# C64_Keyb-Test.net
KiCad netlist of a schematic drawn in EAGLE
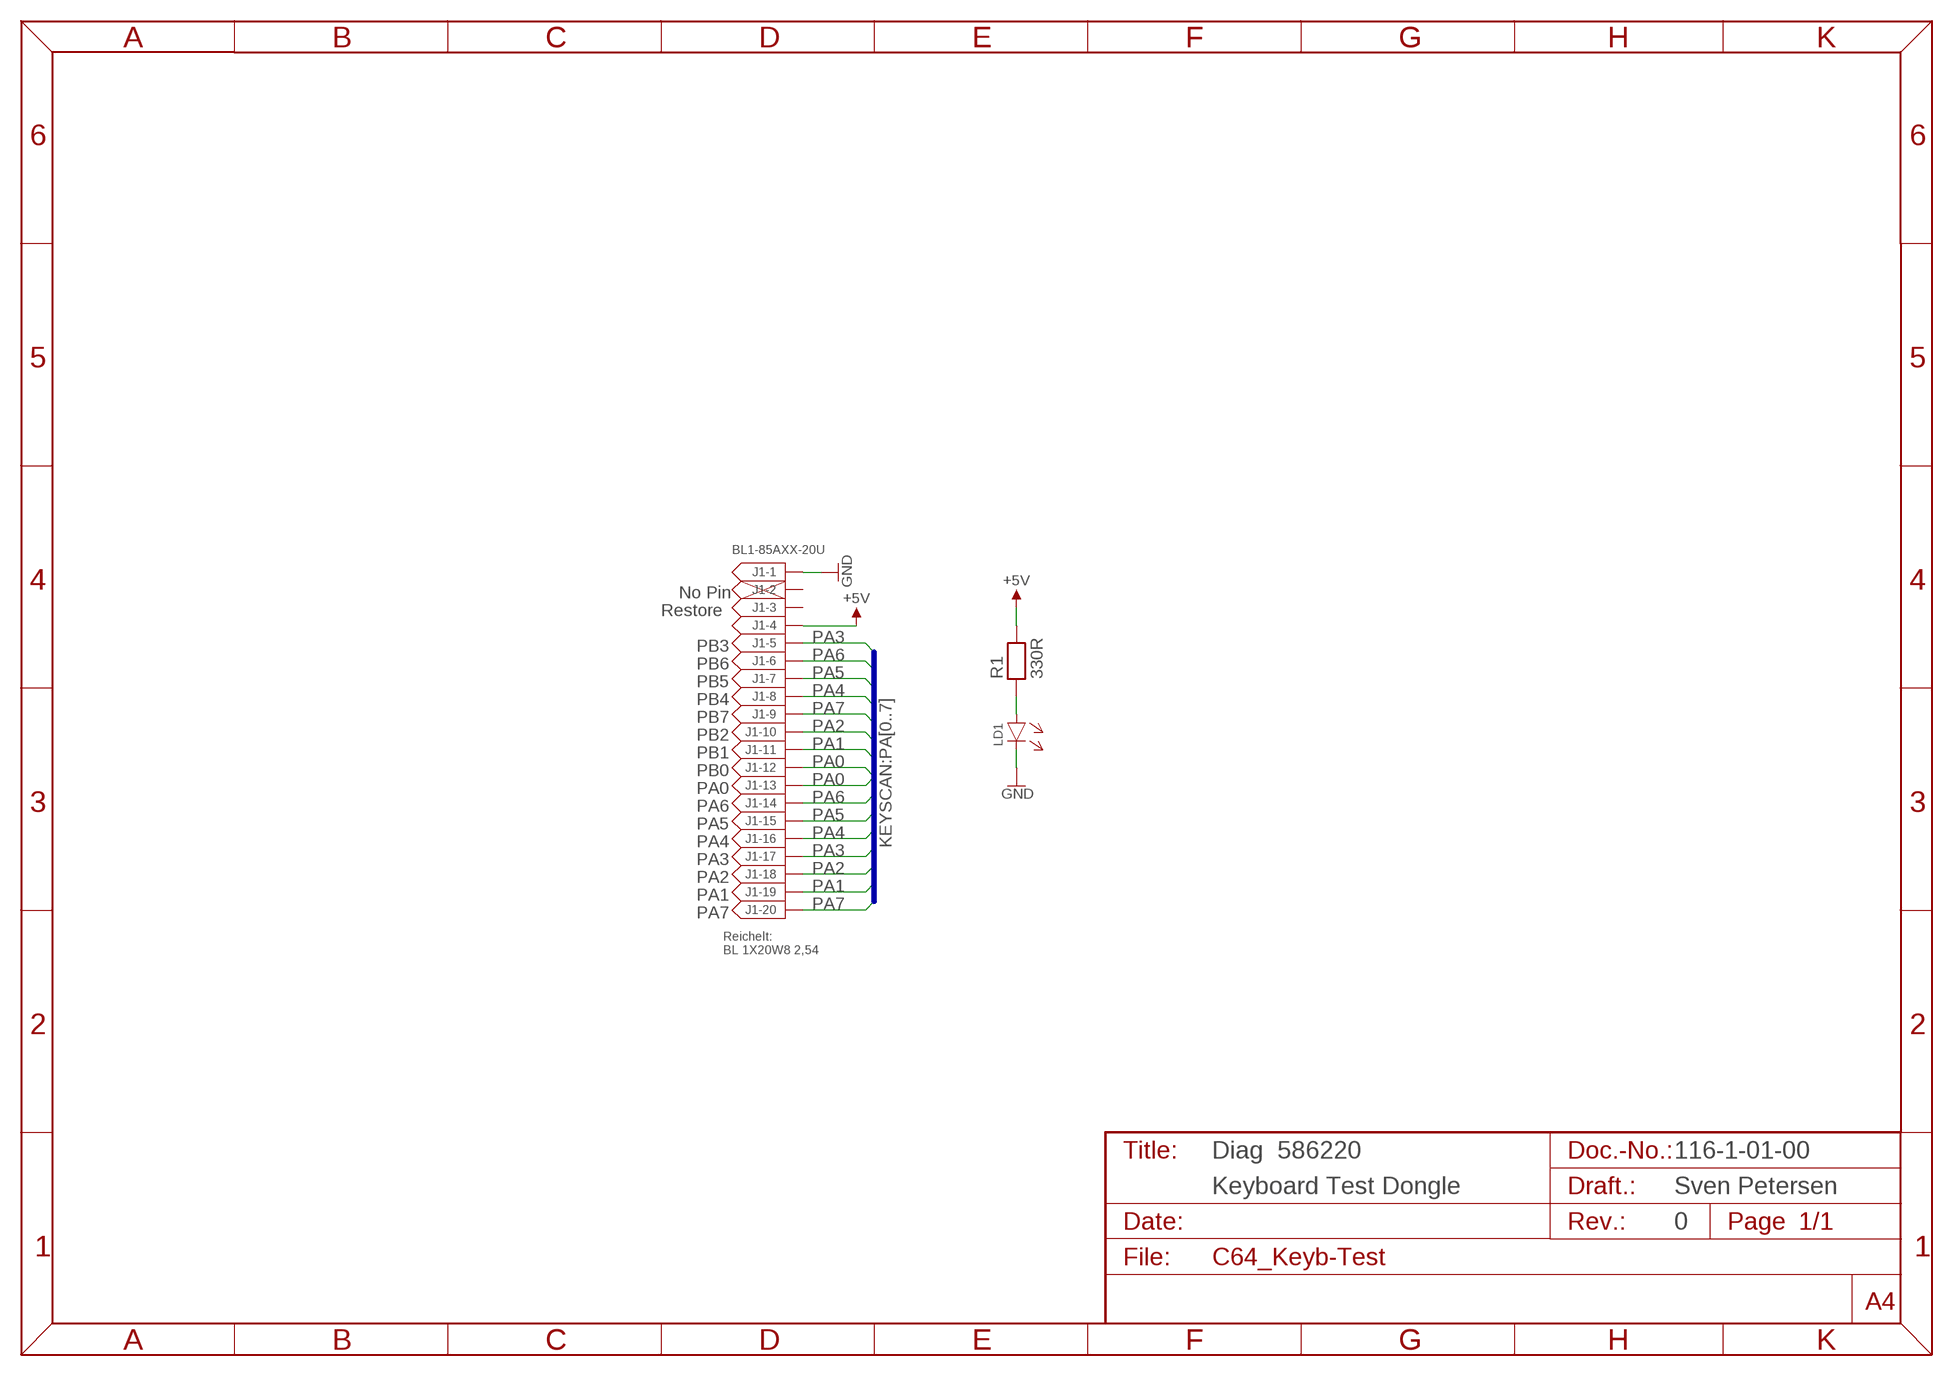
[diagram p0: schematic, sheet 1]

(export (version "E")
  (design (tool "Eeschema 10.0.6"))
  (components
    (comp (ref "J1")
      (value "BL1-85AXX-20U")
      (footprint "eagle-import:BL1-85AXX-20U")
      (libsource (lib "eagle-import") (part "BL1-85AXX-20U"))
    )
    (comp (ref "LD1")
      (value "3MM")
      (footprint "eagle-import:3MM")
      (libsource (lib "eagle-import") (part "3MM"))
    )
    (comp (ref "R1")
      (value "330R")
      (footprint "eagle-import:R-10")
      (libsource (lib "eagle-import") (part "RES04"))
    )
  )
  (nets
    (net (code "9") (name "+5V") (class "Default")
      (node (ref "J1") (pin "4") (pinfunction "1_4") (pintype "bidirectional"))
      (node (ref "R1") (pin "2") (pinfunction "2_2") (pintype "passive"))
    )
    (net (code "11") (name "/PA0") (class "Default")
      (node (ref "J1") (pin "12") (pinfunction "1_12") (pintype "bidirectional"))
      (node (ref "J1") (pin "13") (pinfunction "1_13") (pintype "bidirectional"))
    )
    (net (code "12") (name "/PA1") (class "Default")
      (node (ref "J1") (pin "11") (pinfunction "1_11") (pintype "bidirectional"))
      (node (ref "J1") (pin "19") (pinfunction "1_19") (pintype "bidirectional"))
    )
    (net (code "13") (name "/PA2") (class "Default")
      (node (ref "J1") (pin "10") (pinfunction "1_10") (pintype "bidirectional"))
      (node (ref "J1") (pin "18") (pinfunction "1_18") (pintype "bidirectional"))
    )
    (net (code "14") (name "/PA3") (class "Default")
      (node (ref "J1") (pin "17") (pinfunction "1_17") (pintype "bidirectional"))
      (node (ref "J1") (pin "5") (pinfunction "1_5") (pintype "bidirectional"))
    )
    (net (code "15") (name "/PA4") (class "Default")
      (node (ref "J1") (pin "16") (pinfunction "1_16") (pintype "bidirectional"))
      (node (ref "J1") (pin "8") (pinfunction "1_8") (pintype "bidirectional"))
    )
    (net (code "16") (name "/PA5") (class "Default")
      (node (ref "J1") (pin "15") (pinfunction "1_15") (pintype "bidirectional"))
      (node (ref "J1") (pin "7") (pinfunction "1_7") (pintype "bidirectional"))
    )
    (net (code "17") (name "/PA6") (class "Default")
      (node (ref "J1") (pin "14") (pinfunction "1_14") (pintype "bidirectional"))
      (node (ref "J1") (pin "6") (pinfunction "1_6") (pintype "bidirectional"))
    )
    (net (code "18") (name "/PA7") (class "Default")
      (node (ref "J1") (pin "20") (pinfunction "1_20") (pintype "bidirectional"))
      (node (ref "J1") (pin "9") (pinfunction "1_9") (pintype "bidirectional"))
    )
    (net (code "19") (name "GND") (class "Default")
      (node (ref "J1") (pin "1") (pinfunction "1_1") (pintype "bidirectional"))
      (node (ref "LD1") (pin "C") (pinfunction "K_C") (pintype "bidirectional"))
    )
    (net (code "20") (name "Net-(LD1-PadA)") (class "Default")
      (node (ref "LD1") (pin "A") (pinfunction "A_A") (pintype "bidirectional"))
      (node (ref "R1") (pin "1") (pinfunction "1_1") (pintype "passive"))
    )
    (net (code "21") (name "unconnected-(J1L-1-Pad2)") (class "Default")
      (node (ref "J1") (pin "2") (pinfunction "1_2") (pintype "bidirectional"))
    )
    (net (code "22") (name "unconnected-(J1N-1-Pad3)") (class "Default")
      (node (ref "J1") (pin "3") (pinfunction "1_3") (pintype "bidirectional"))
    )
  )
)
